# high_pwr_regulator.net
KiCad netlist of a schematic drawn in EAGLE
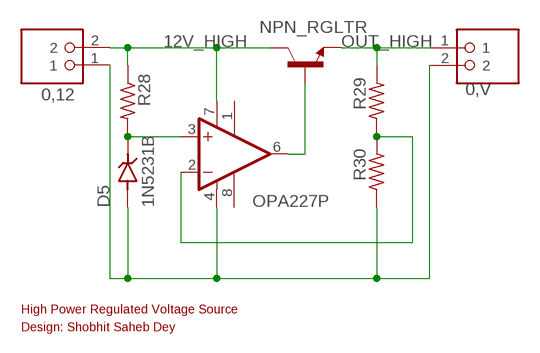
[diagram p0: schematic, sheet 1]

(export (version "E")
  (design (tool "Eeschema 10.0.6"))
  (components
    (comp (ref "0,12")
      (value "1935161")
      (footprint "eagle-import:PHOENIX_1935161")
      (fields (field (name "MF") "Phoenix Contact"))
      (libsource (lib "eagle-import") (part "1935161"))
    )
    (comp (ref "0,V")
      (value "1935161")
      (footprint "eagle-import:PHOENIX_1935161")
      (fields (field (name "MF") "Phoenix Contact"))
      (libsource (lib "eagle-import") (part "1935161"))
    )
    (comp (ref "D5")
      (value "1N5231B")
      (footprint "eagle-import:DIOAD928W47L399D179")
      (fields (field (name "MF") "Taiwan Semiconductor"))
      (libsource (lib "eagle-import") (part "1N5231B"))
    )
    (comp (ref "NPN_RGLTR")
      (value "NJD2873T4G")
      (footprint "eagle-import:TO229P990X238-3N")
      (fields (field (name "MF") "ON Semiconductor"))
      (libsource (lib "eagle-import") (part "NJD2873T4G"))
    )
    (comp (ref "OP_FAN")
      (value "OPA227P")
      (footprint "eagle-import:DIL08")
      (libsource (lib "eagle-import") (part "OPA22P7"))
    )
    (comp (ref "R28")
      (value "R-US_0411/3V")
      (footprint "eagle-import:0411V")
      (libsource (lib "eagle-import") (part "R-US_0411/3V"))
    )
    (comp (ref "R29")
      (value "R-US_0411/3V")
      (footprint "eagle-import:0411V")
      (libsource (lib "eagle-import") (part "R-US_0411/3V"))
    )
    (comp (ref "R30")
      (value "R-US_0411/3V")
      (footprint "eagle-import:0411V")
      (libsource (lib "eagle-import") (part "R-US_0411/3V"))
    )
  )
  (nets
    (net (code "1") (name "/12V_HIGH") (class "Default")
      (node (ref "0,12") (pin "2") (pinfunction "2_2") (pintype "passive"))
      (node (ref "NPN_RGLTR") (pin "4") (pinfunction "C_4") (pintype "passive"))
      (node (ref "OP_FAN") (pin "7") (pinfunction "V+_7") (pintype "power_in"))
      (node (ref "R28") (pin "1") (pinfunction "1_1") (pintype "passive"))
    )
    (net (code "2") (name "/OUT_HIGH") (class "Default")
      (node (ref "0,V") (pin "1") (pinfunction "1_1") (pintype "passive"))
      (node (ref "NPN_RGLTR") (pin "3") (pinfunction "E_3") (pintype "passive"))
      (node (ref "R29") (pin "2") (pinfunction "2_2") (pintype "passive"))
    )
    (net (code "3") (name "Net-(D5-K)") (class "Default")
      (node (ref "D5") (pin "C") (pinfunction "K_C") (pintype "passive"))
      (node (ref "OP_FAN") (pin "3") (pinfunction "+IN_3") (pintype "input"))
      (node (ref "R28") (pin "2") (pinfunction "2_2") (pintype "passive"))
    )
    (net (code "4") (name "Net-(NPN_RGLTR-B)") (class "Default")
      (node (ref "NPN_RGLTR") (pin "1") (pinfunction "B_1") (pintype "passive"))
      (node (ref "OP_FAN") (pin "6") (pinfunction "OUT_6") (pintype "output"))
    )
    (net (code "5") (name "Net-(OP_FAN--IN)") (class "Default")
      (node (ref "OP_FAN") (pin "2") (pinfunction "-IN_2") (pintype "input"))
      (node (ref "R29") (pin "1") (pinfunction "1_1") (pintype "passive"))
      (node (ref "R30") (pin "2") (pinfunction "2_2") (pintype "passive"))
    )
    (net (code "6") (name "Net-(OP_FAN-V-)") (class "Default")
      (node (ref "0,12") (pin "1") (pinfunction "1_1") (pintype "passive"))
      (node (ref "0,V") (pin "2") (pinfunction "2_2") (pintype "passive"))
      (node (ref "D5") (pin "A") (pinfunction "A_A") (pintype "passive"))
      (node (ref "OP_FAN") (pin "4") (pinfunction "V-_4") (pintype "power_in"))
      (node (ref "R30") (pin "1") (pinfunction "1_1") (pintype "passive"))
    )
    (net (code "7") (name "unconnected-(OP_FAN-OFF1-Pad1)") (class "Default")
      (node (ref "OP_FAN") (pin "1") (pinfunction "OFF1_1") (pintype "passive"))
    )
    (net (code "8") (name "unconnected-(OP_FAN-OFF2-Pad8)") (class "Default")
      (node (ref "OP_FAN") (pin "8") (pinfunction "OFF2_8") (pintype "passive"))
    )
  )
)
